# esp-wroom-test.net
KiCad netlist of a schematic drawn in EAGLE
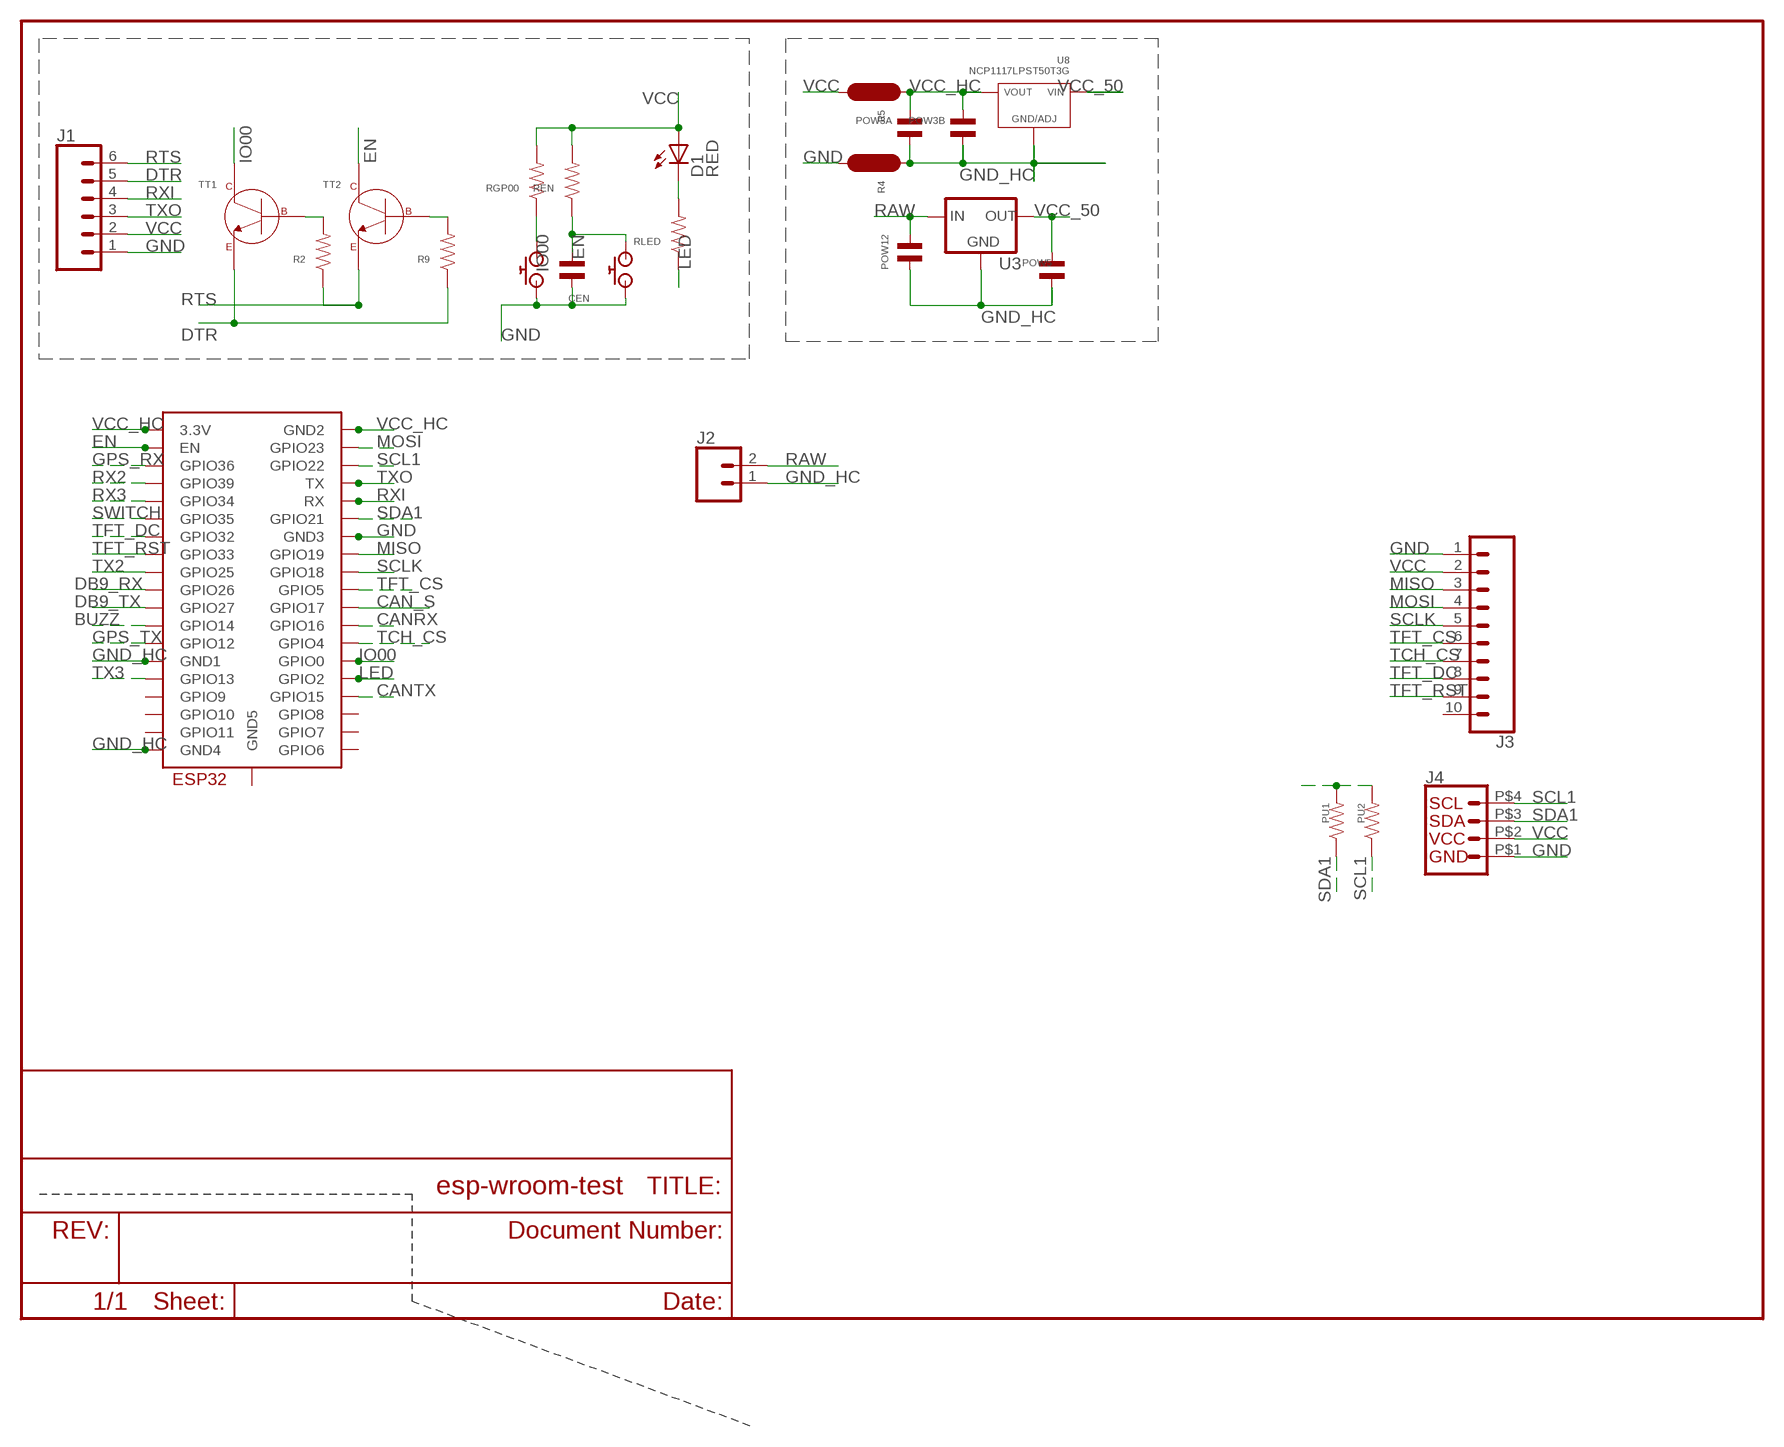
[diagram p0: schematic, sheet 1]

(export (version "E")
  (design (tool "Eeschema 10.0.6"))
  (components
    (comp (ref "CEN")
      (value "CAPACITOR_NP_1206")
      (footprint "eagle-import:C1206")
      (libsource (lib "eagle-import") (part "CAPACITOR_NP_1206"))
    )
    (comp (ref "D1")
      (value "RED")
      (footprint "eagle-import:LED-1206")
      (libsource (lib "eagle-import") (part "LED-REDLILYPAD"))
    )
    (comp (ref "J1")
      (value "CONN_06")
      (footprint "eagle-import:1X6-1.25MM-SMD")
      (libsource (lib "eagle-import") (part "CONN_06"))
    )
    (comp (ref "J2")
      (value "CONN_02")
      (footprint "eagle-import:1X02")
      (libsource (lib "eagle-import") (part "CONN_02"))
    )
    (comp (ref "J3")
      (value "CONN_10")
      (footprint "eagle-import:1X10-1.25MM")
      (libsource (lib "eagle-import") (part "CONN_10"))
    )
    (comp (ref "J4")
      (value "Vertical Qwiic Connector")
      (footprint "eagle-import:JST04_1MM_HOLES")
      (libsource (lib "eagle-import") (part "QWIIC_CONNECTORJST04_1MM_HOLE"))
    )
    (comp (ref "POW3A")
      (value "CAPACITOR_NP_1206")
      (footprint "eagle-import:C1206")
      (libsource (lib "eagle-import") (part "CAPACITOR_NP_1206"))
    )
    (comp (ref "POW3B")
      (value "CAPACITOR_NP_1206")
      (footprint "eagle-import:C1206")
      (libsource (lib "eagle-import") (part "CAPACITOR_NP_1206"))
    )
    (comp (ref "POW5")
      (value "CAPACITOR_NP_1206")
      (footprint "eagle-import:C1206")
      (libsource (lib "eagle-import") (part "CAPACITOR_NP_1206"))
    )
    (comp (ref "POW12")
      (value "CAPACITOR_NP_1206")
      (footprint "eagle-import:C1206")
      (libsource (lib "eagle-import") (part "CAPACITOR_NP_1206"))
    )
    (comp (ref "PU1")
      (value "RESISTOR_1206")
      (footprint "eagle-import:R1206")
      (libsource (lib "eagle-import") (part "RESISTOR_1206"))
    )
    (comp (ref "PU2")
      (value "RESISTOR_1206")
      (footprint "eagle-import:R1206")
      (libsource (lib "eagle-import") (part "RESISTOR_1206"))
    )
    (comp (ref "R2")
      (value "RESISTOR_1206")
      (footprint "eagle-import:R1206")
      (libsource (lib "eagle-import") (part "RESISTOR_1206"))
    )
    (comp (ref "R4")
      (value "JUMPER")
      (footprint "eagle-import:R0603_JMP")
      (libsource (lib "eagle-import") (part "JUMPER"))
    )
    (comp (ref "R5")
      (value "JUMPER")
      (footprint "eagle-import:R0603_JMP")
      (libsource (lib "eagle-import") (part "JUMPER"))
    )
    (comp (ref "R9")
      (value "RESISTOR_1206")
      (footprint "eagle-import:R1206")
      (libsource (lib "eagle-import") (part "RESISTOR_1206"))
    )
    (comp (ref "REN")
      (value "RESISTOR_1206")
      (footprint "eagle-import:R1206")
      (libsource (lib "eagle-import") (part "RESISTOR_1206"))
    )
    (comp (ref "RGP00")
      (value "RESISTOR_1206")
      (footprint "eagle-import:R1206")
      (libsource (lib "eagle-import") (part "RESISTOR_1206"))
    )
    (comp (ref "RLED")
      (value "RESISTOR_1206")
      (footprint "eagle-import:R1206")
      (libsource (lib "eagle-import") (part "RESISTOR_1206"))
    )
    (comp (ref "SW1")
      (value "AMAZON_BUTTONB2010")
      (footprint "eagle-import:C2010")
      (libsource (lib "eagle-import") (part "AMAZON_BUTTONB2010"))
    )
    (comp (ref "SW2")
      (value "AMAZON_BUTTONB2010")
      (footprint "eagle-import:C2010")
      (libsource (lib "eagle-import") (part "AMAZON_BUTTONB2010"))
    )
    (comp (ref "TT1")
      (value "MF-DSC-SOT233-MMBT3904")
      (footprint "eagle-import:SOT-23-3")
      (fields (field (name "HOUSEPART") "YES"))
      (libsource (lib "eagle-import") (part "NPN_BJT_SOT-23-3MMBT3904"))
    )
    (comp (ref "TT2")
      (value "MF-DSC-SOT233-MMBT3904")
      (footprint "eagle-import:SOT-23-3")
      (fields (field (name "HOUSEPART") "YES"))
      (libsource (lib "eagle-import") (part "NPN_BJT_SOT-23-3MMBT3904"))
    )
    (comp (ref "U$3")
      (value "ESP32-WROOM")
      (footprint "eagle-import:ESP32-WROOM")
      (libsource (lib "eagle-import") (part "ESP32-WROOM"))
    )
    (comp (ref "U3")
      (value "V_REG_78XXSINK")
      (footprint "eagle-import:TO220-IGO")
      (libsource (lib "eagle-import") (part "V_REG_78XXSINK"))
    )
    (comp (ref "U8")
      (value "NCP1117LPST50T3G")
      (footprint "eagle-import:SOT-223-3")
      (fields (field (name "HOUSEPART") "NO"))
      (libsource (lib "eagle-import") (part "NCP1117LPST50T3G"))
    )
  )
  (nets
    (net (code "1") (name "/BUZZ") (class "Default")
      (node (ref "U$3") (pin "IO14") (pinfunction "GPIO14_IO14") (pintype "bidirectional"))
    )
    (net (code "2") (name "/CANRX") (class "Default")
      (node (ref "U$3") (pin "IO16") (pinfunction "GPIO16_IO16") (pintype "bidirectional"))
    )
    (net (code "3") (name "/CANTX") (class "Default")
      (node (ref "U$3") (pin "IO15") (pinfunction "GPIO15_IO15") (pintype "bidirectional"))
    )
    (net (code "4") (name "/CAN_S") (class "Default")
      (node (ref "U$3") (pin "IO17") (pinfunction "GPIO17_IO17") (pintype "bidirectional"))
    )
    (net (code "5") (name "/DB9_RX") (class "Default")
      (node (ref "U$3") (pin "IO26") (pinfunction "GPIO26_IO26") (pintype "bidirectional"))
    )
    (net (code "6") (name "/DB9_TX") (class "Default")
      (node (ref "U$3") (pin "IO27") (pinfunction "GPIO27_IO27") (pintype "bidirectional"))
    )
    (net (code "7") (name "/DTR") (class "Default")
      (node (ref "J1") (pin "5") (pinfunction "5_5") (pintype "passive"))
      (node (ref "R9") (pin "P$1") (pinfunction "P$1_P$1") (pintype "passive"))
      (node (ref "TT1") (pin "P$2") (pinfunction "EMITTER_P$2") (pintype "bidirectional"))
    )
    (net (code "8") (name "/EN") (class "Default")
      (node (ref "CEN") (pin "P$1") (pinfunction "P$1_P$1") (pintype "passive"))
      (node (ref "REN") (pin "P$1") (pinfunction "P$1_P$1") (pintype "passive"))
      (node (ref "SW1") (pin "P$1") (pinfunction "P$1_P$1") (pintype "bidirectional"))
      (node (ref "TT2") (pin "P$3") (pinfunction "COLLECTOR_P$3") (pintype "bidirectional"))
      (node (ref "U$3") (pin "EN") (pinfunction "EN_EN") (pintype "bidirectional"))
    )
    (net (code "9") (name "/GND") (class "Default")
      (node (ref "CEN") (pin "P$2") (pinfunction "P$2_P$2") (pintype "passive"))
      (node (ref "J1") (pin "1") (pinfunction "1_1") (pintype "passive"))
      (node (ref "J3") (pin "1") (pinfunction "1_1") (pintype "passive"))
      (node (ref "J4") (pin "P$1") (pinfunction "1_P$1") (pintype "power_in"))
      (node (ref "R4") (pin "P$2") (pinfunction "P$2_P$2") (pintype "passive"))
      (node (ref "SW1") (pin "P$2") (pinfunction "P$2_P$2") (pintype "bidirectional"))
      (node (ref "SW2") (pin "P$2") (pinfunction "P$2_P$2") (pintype "bidirectional"))
      (node (ref "U$3") (pin "GND3") (pinfunction "GND3_GND3") (pintype "bidirectional"))
    )
    (net (code "10") (name "/GND_HC") (class "Default")
      (node (ref "J2") (pin "1") (pinfunction "1_1") (pintype "passive"))
      (node (ref "POW12") (pin "P$2") (pinfunction "P$2_P$2") (pintype "passive"))
      (node (ref "POW3A") (pin "P$2") (pinfunction "P$2_P$2") (pintype "passive"))
      (node (ref "POW3B") (pin "P$2") (pinfunction "P$2_P$2") (pintype "passive"))
      (node (ref "POW5") (pin "P$2") (pinfunction "P$2_P$2") (pintype "passive"))
      (node (ref "R4") (pin "P$1") (pinfunction "P$1_P$1") (pintype "passive"))
      (node (ref "U$3") (pin "GND1") (pinfunction "GND1_GND1") (pintype "bidirectional"))
      (node (ref "U$3") (pin "GND4") (pinfunction "GND4_GND4") (pintype "bidirectional"))
      (node (ref "U3") (pin "GND") (pinfunction "GND_GND") (pintype "input"))
      (node (ref "U8") (pin "P$2") (pinfunction "GND/ADJ_P$2") (pintype "bidirectional"))
    )
    (net (code "11") (name "/GPS_RX") (class "Default")
      (node (ref "U$3") (pin "SENSOR_VP") (pinfunction "GPIO36_SENSOR_VP") (pintype "bidirectional"))
    )
    (net (code "12") (name "/GPS_TX") (class "Default")
      (node (ref "U$3") (pin "IO12") (pinfunction "GPIO12_IO12") (pintype "bidirectional"))
    )
    (net (code "13") (name "/IO00") (class "Default")
      (node (ref "RGP00") (pin "P$1") (pinfunction "P$1_P$1") (pintype "passive"))
      (node (ref "SW2") (pin "P$1") (pinfunction "P$1_P$1") (pintype "bidirectional"))
      (node (ref "TT1") (pin "P$3") (pinfunction "COLLECTOR_P$3") (pintype "bidirectional"))
      (node (ref "U$3") (pin "IO0") (pinfunction "GPIO0_IO0") (pintype "bidirectional"))
    )
    (net (code "14") (name "/LED") (class "Default")
      (node (ref "RLED") (pin "P$1") (pinfunction "P$1_P$1") (pintype "passive"))
      (node (ref "U$3") (pin "IO2") (pinfunction "GPIO2_IO2") (pintype "bidirectional"))
    )
    (net (code "15") (name "/MISO") (class "Default")
      (node (ref "J3") (pin "3") (pinfunction "3_3") (pintype "passive"))
      (node (ref "U$3") (pin "IO19") (pinfunction "GPIO19_IO19") (pintype "bidirectional"))
    )
    (net (code "16") (name "/MOSI") (class "Default")
      (node (ref "J3") (pin "4") (pinfunction "4_4") (pintype "passive"))
      (node (ref "U$3") (pin "IO23") (pinfunction "GPIO23_IO23") (pintype "bidirectional"))
    )
    (net (code "17") (name "/RAW") (class "Default")
      (node (ref "J2") (pin "2") (pinfunction "2_2") (pintype "passive"))
      (node (ref "POW12") (pin "P$1") (pinfunction "P$1_P$1") (pintype "passive"))
      (node (ref "U3") (pin "IN") (pinfunction "IN_IN") (pintype "input"))
    )
    (net (code "18") (name "/RTS") (class "Default")
      (node (ref "J1") (pin "6") (pinfunction "6_6") (pintype "passive"))
      (node (ref "R2") (pin "P$1") (pinfunction "P$1_P$1") (pintype "passive"))
      (node (ref "TT2") (pin "P$2") (pinfunction "EMITTER_P$2") (pintype "bidirectional"))
    )
    (net (code "19") (name "/RX2") (class "Default")
      (node (ref "U$3") (pin "SENSOR_VN") (pinfunction "GPIO39_SENSOR_VN") (pintype "bidirectional"))
    )
    (net (code "20") (name "/RX3") (class "Default")
      (node (ref "U$3") (pin "IO34") (pinfunction "GPIO34_IO34") (pintype "bidirectional"))
    )
    (net (code "21") (name "/RXI") (class "Default")
      (node (ref "J1") (pin "4") (pinfunction "4_4") (pintype "passive"))
      (node (ref "U$3") (pin "RX") (pinfunction "RX_RX") (pintype "bidirectional"))
    )
    (net (code "22") (name "/SCL1") (class "Default")
      (node (ref "J4") (pin "P$4") (pinfunction "4_P$4") (pintype "passive"))
      (node (ref "PU2") (pin "P$1") (pinfunction "P$1_P$1") (pintype "passive"))
      (node (ref "U$3") (pin "IO22") (pinfunction "GPIO22_IO22") (pintype "bidirectional"))
    )
    (net (code "23") (name "/SCLK") (class "Default")
      (node (ref "J3") (pin "5") (pinfunction "5_5") (pintype "passive"))
      (node (ref "U$3") (pin "IO18") (pinfunction "GPIO18_IO18") (pintype "bidirectional"))
    )
    (net (code "24") (name "/SDA1") (class "Default")
      (node (ref "J4") (pin "P$3") (pinfunction "3_P$3") (pintype "passive"))
      (node (ref "PU1") (pin "P$1") (pinfunction "P$1_P$1") (pintype "passive"))
      (node (ref "U$3") (pin "IO21") (pinfunction "GPIO21_IO21") (pintype "bidirectional"))
    )
    (net (code "25") (name "/SWITCH") (class "Default")
      (node (ref "U$3") (pin "IO35") (pinfunction "GPIO35_IO35") (pintype "bidirectional"))
    )
    (net (code "26") (name "/TCH_CS") (class "Default")
      (node (ref "J3") (pin "7") (pinfunction "7_7") (pintype "passive"))
      (node (ref "U$3") (pin "IO4") (pinfunction "GPIO4_IO4") (pintype "bidirectional"))
    )
    (net (code "27") (name "/TFT_CS") (class "Default")
      (node (ref "J3") (pin "6") (pinfunction "6_6") (pintype "passive"))
      (node (ref "U$3") (pin "IO5") (pinfunction "GPIO5_IO5") (pintype "bidirectional"))
    )
    (net (code "28") (name "/TFT_DC") (class "Default")
      (node (ref "J3") (pin "8") (pinfunction "8_8") (pintype "passive"))
      (node (ref "U$3") (pin "IO32") (pinfunction "GPIO32_IO32") (pintype "bidirectional"))
    )
    (net (code "29") (name "/TFT_RST") (class "Default")
      (node (ref "J3") (pin "9") (pinfunction "9_9") (pintype "passive"))
      (node (ref "U$3") (pin "IO33") (pinfunction "GPIO33_IO33") (pintype "bidirectional"))
    )
    (net (code "30") (name "/TX2") (class "Default")
      (node (ref "U$3") (pin "IO25") (pinfunction "GPIO25_IO25") (pintype "bidirectional"))
    )
    (net (code "31") (name "/TX3") (class "Default")
      (node (ref "U$3") (pin "IO13") (pinfunction "GPIO13_IO13") (pintype "bidirectional"))
    )
    (net (code "32") (name "/TXO") (class "Default")
      (node (ref "J1") (pin "3") (pinfunction "3_3") (pintype "passive"))
      (node (ref "U$3") (pin "TX") (pinfunction "TX_TX") (pintype "bidirectional"))
    )
    (net (code "33") (name "/VCC") (class "Default")
      (node (ref "D1") (pin "A") (pinfunction "A_A") (pintype "passive"))
      (node (ref "J1") (pin "2") (pinfunction "2_2") (pintype "passive"))
      (node (ref "J3") (pin "2") (pinfunction "2_2") (pintype "passive"))
      (node (ref "J4") (pin "P$2") (pinfunction "2_P$2") (pintype "power_in"))
      (node (ref "PU1") (pin "P$2") (pinfunction "P$2_P$2") (pintype "passive"))
      (node (ref "PU2") (pin "P$2") (pinfunction "P$2_P$2") (pintype "passive"))
      (node (ref "R5") (pin "P$2") (pinfunction "P$2_P$2") (pintype "passive"))
      (node (ref "REN") (pin "P$2") (pinfunction "P$2_P$2") (pintype "passive"))
      (node (ref "RGP00") (pin "P$2") (pinfunction "P$2_P$2") (pintype "passive"))
    )
    (net (code "34") (name "/VCC_50") (class "Default")
      (node (ref "POW5") (pin "P$1") (pinfunction "P$1_P$1") (pintype "passive"))
      (node (ref "U3") (pin "OUT") (pinfunction "OUT_OUT") (pintype "passive"))
      (node (ref "U8") (pin "P$4") (pinfunction "VIN_P$4") (pintype "bidirectional"))
    )
    (net (code "35") (name "/VCC_HC") (class "Default")
      (node (ref "POW3A") (pin "P$1") (pinfunction "P$1_P$1") (pintype "passive"))
      (node (ref "POW3B") (pin "P$1") (pinfunction "P$1_P$1") (pintype "passive"))
      (node (ref "R5") (pin "P$1") (pinfunction "P$1_P$1") (pintype "passive"))
      (node (ref "U$3") (pin "3V3") (pinfunction "3.3V_3V3") (pintype "bidirectional"))
      (node (ref "U$3") (pin "GND2") (pinfunction "GND2_GND2") (pintype "bidirectional"))
      (node (ref "U8") (pin "P$1") (pinfunction "VOUT_P$1") (pintype "bidirectional"))
      (node (ref "U8") (pin "P$3") (pinfunction "VOUT_P$3") (pintype "bidirectional"))
    )
    (net (code "36") (name "Net-(D1-PadC)") (class "Default")
      (node (ref "D1") (pin "C") (pinfunction "C_C") (pintype "passive"))
      (node (ref "RLED") (pin "P$2") (pinfunction "P$2_P$2") (pintype "passive"))
    )
    (net (code "37") (name "Net-(TT1-BASE)") (class "Default")
      (node (ref "R2") (pin "P$2") (pinfunction "P$2_P$2") (pintype "passive"))
      (node (ref "TT1") (pin "P$1") (pinfunction "BASE_P$1") (pintype "bidirectional"))
    )
    (net (code "38") (name "Net-(TT2-BASE)") (class "Default")
      (node (ref "R9") (pin "P$2") (pinfunction "P$2_P$2") (pintype "passive"))
      (node (ref "TT2") (pin "P$1") (pinfunction "BASE_P$1") (pintype "bidirectional"))
    )
    (net (code "39") (name "unconnected-(J3-Pad10)") (class "Default")
      (node (ref "J3") (pin "10") (pinfunction "10_10") (pintype "passive"))
    )
    (net (code "40") (name "unconnected-(U$3-GPIO6-PadCLK)") (class "Default")
      (node (ref "U$3") (pin "CLK") (pinfunction "GPIO6_CLK") (pintype "bidirectional"))
    )
    (net (code "41") (name "unconnected-(U$3-GPIO7-PadSD0)") (class "Default")
      (node (ref "U$3") (pin "SD0") (pinfunction "GPIO7_SD0") (pintype "bidirectional"))
    )
    (net (code "42") (name "unconnected-(U$3-GPIO8-PadSD1)") (class "Default")
      (node (ref "U$3") (pin "SD1") (pinfunction "GPIO8_SD1") (pintype "bidirectional"))
    )
    (net (code "43") (name "unconnected-(U$3-GPIO9-PadSD2)") (class "Default")
      (node (ref "U$3") (pin "SD2") (pinfunction "GPIO9_SD2") (pintype "bidirectional"))
    )
    (net (code "44") (name "unconnected-(U$3-GPIO10-PadSD3)") (class "Default")
      (node (ref "U$3") (pin "SD3") (pinfunction "GPIO10_SD3") (pintype "bidirectional"))
    )
    (net (code "45") (name "unconnected-(U$3-GPIO11-PadCMD)") (class "Default")
      (node (ref "U$3") (pin "CMD") (pinfunction "GPIO11_CMD") (pintype "bidirectional"))
    )
    (net (code "46") (name "unconnected-(U$3-PadGND5)") (class "Default")
      (node (ref "U$3") (pin "GND5") (pinfunction "GND5_GND5") (pintype "bidirectional"))
    )
  )
)
